# PatientBedAdapter.net
KiCad netlist of a schematic drawn in EAGLE
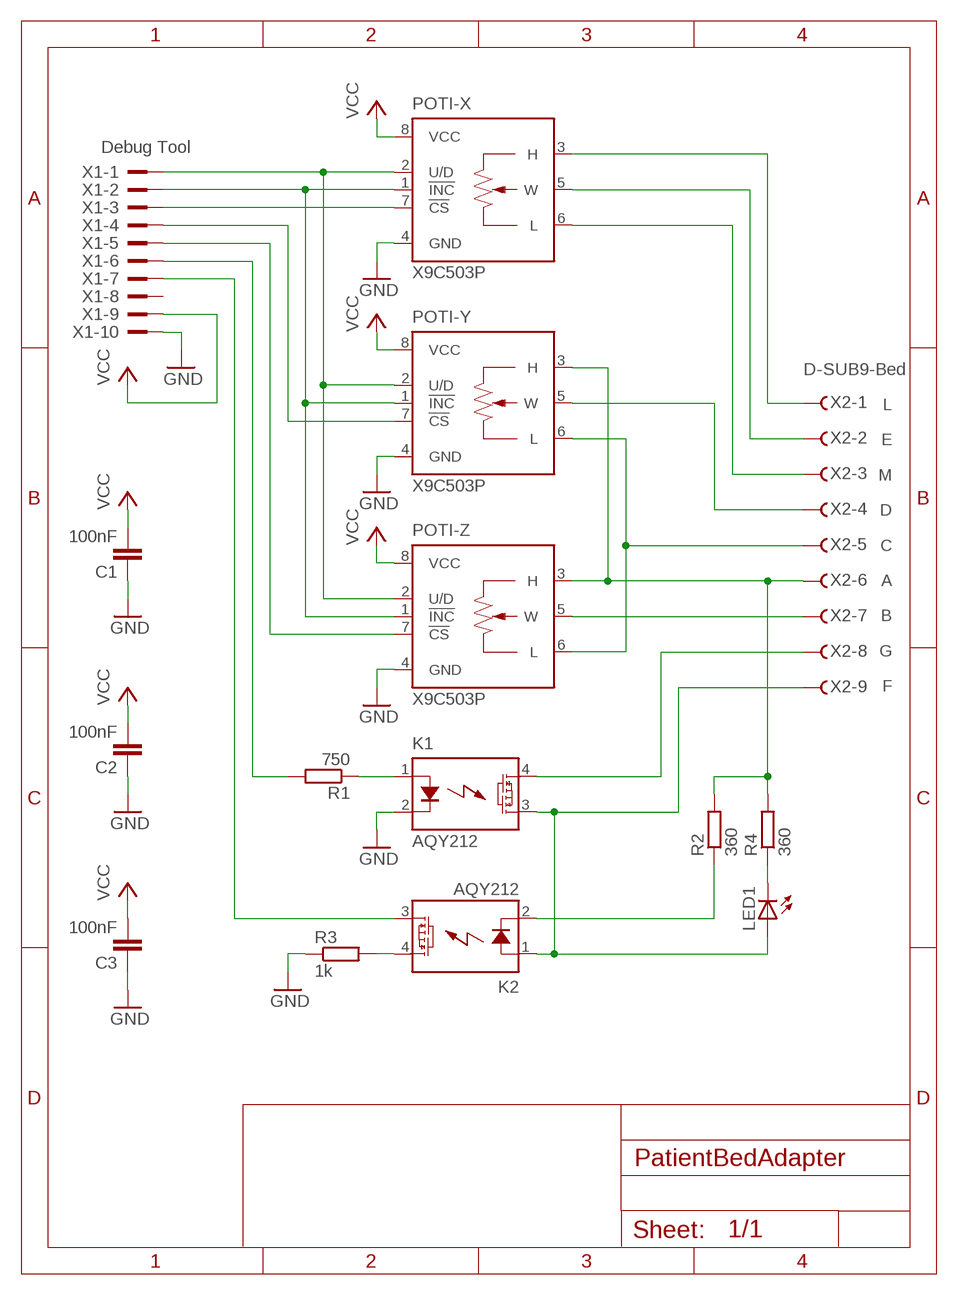
[diagram p0: schematic, sheet 1]

(export (version "E")
  (design (tool "Eeschema 10.0.6"))
  (components
    (comp (ref "C1")
      (value "100nF")
      (footprint "eagle-import:C050-024X044")
      (libsource (lib "eagle-import") (part "C-EU050-024X044"))
    )
    (comp (ref "C2")
      (value "100nF")
      (footprint "eagle-import:C050-024X044")
      (libsource (lib "eagle-import") (part "C-EU050-024X044"))
    )
    (comp (ref "C3")
      (value "100nF")
      (footprint "eagle-import:C050-024X044")
      (libsource (lib "eagle-import") (part "C-EU050-024X044"))
    )
    (comp (ref "K1")
      (value "AQY212")
      (footprint "eagle-import:SOP04")
      (libsource (lib "eagle-import") (part "AQYSOP21"))
    )
    (comp (ref "K2")
      (value "AQY212")
      (footprint "eagle-import:SOP04")
      (libsource (lib "eagle-import") (part "AQYSOP21"))
    )
    (comp (ref "LED1")
      (value "LED3MM")
      (footprint "eagle-import:LED3MM")
      (libsource (lib "eagle-import") (part "LED3MM"))
    )
    (comp (ref "POTI-X")
      (value "X9C503P")
      (footprint "eagle-import:DIL08")
      (fields (field (name "MF") "INTERSIL") (field (name "MPN") "X9C102P"))
      (libsource (lib "eagle-import") (part "X9C102P"))
    )
    (comp (ref "POTI-Y")
      (value "X9C503P")
      (footprint "eagle-import:DIL08")
      (fields (field (name "MF") "INTERSIL") (field (name "MPN") "X9C102P"))
      (libsource (lib "eagle-import") (part "X9C102P"))
    )
    (comp (ref "POTI-Z")
      (value "X9C503P")
      (footprint "eagle-import:DIL08")
      (fields (field (name "MF") "INTERSIL") (field (name "MPN") "X9C102P"))
      (libsource (lib "eagle-import") (part "X9C102P"))
    )
    (comp (ref "R1")
      (value "750")
      (footprint "eagle-import:R1206")
      (libsource (lib "eagle-import") (part "R-EU_R1206"))
    )
    (comp (ref "R2")
      (value "360")
      (footprint "eagle-import:R1206")
      (libsource (lib "eagle-import") (part "R-EU_R1206"))
    )
    (comp (ref "R3")
      (value "1k")
      (footprint "eagle-import:R1206")
      (libsource (lib "eagle-import") (part "R-EU_R1206"))
    )
    (comp (ref "R4")
      (value "360")
      (footprint "eagle-import:R1206")
      (libsource (lib "eagle-import") (part "R-EU_R1206"))
    )
    (comp (ref "X1")
      (value "Debug Tool")
      (footprint "eagle-import:PAK100_2500-10")
      (fields (field (name "MF") "3M") (field (name "MPN") "2510-6002UB"))
      (libsource (lib "eagle-import") (part "2510-"))
    )
    (comp (ref "X2")
      (value "D-SUB9-Bed")
      (footprint "eagle-import:H5M09RA")
      (libsource (lib "eagle-import") (part "D-SUB9-H5M09RA"))
    )
  )
  (nets
    (net (code "1") (name "GND") (class "Default")
      (node (ref "C1") (pin "1") (pinfunction "1_1") (pintype "passive"))
      (node (ref "C2") (pin "1") (pinfunction "1_1") (pintype "passive"))
      (node (ref "C3") (pin "1") (pinfunction "1_1") (pintype "passive"))
      (node (ref "K1") (pin "2") (pinfunction "K_2") (pintype "passive"))
      (node (ref "POTI-X") (pin "4") (pinfunction "GND_4") (pintype "power_in"))
      (node (ref "POTI-Y") (pin "4") (pinfunction "GND_4") (pintype "power_in"))
      (node (ref "POTI-Z") (pin "4") (pinfunction "GND_4") (pintype "power_in"))
      (node (ref "R3") (pin "1") (pinfunction "1_1") (pintype "passive"))
      (node (ref "X1") (pin "10") (pinfunction "KL_10") (pintype "passive"))
    )
    (net (code "2") (name "Net-(K1-A)") (class "Default")
      (node (ref "K1") (pin "1") (pinfunction "A_1") (pintype "passive"))
      (node (ref "R1") (pin "1") (pinfunction "1_1") (pintype "passive"))
    )
    (net (code "3") (name "Net-(K1-DS1)") (class "Default")
      (node (ref "K1") (pin "4") (pinfunction "DS1_4") (pintype "passive"))
      (node (ref "X2") (pin "8") (pinfunction "F_8") (pintype "passive"))
    )
    (net (code "4") (name "Net-(K1-DS2)") (class "Default")
      (node (ref "K1") (pin "3") (pinfunction "DS2_3") (pintype "passive"))
      (node (ref "K2") (pin "1") (pinfunction "A_1") (pintype "passive"))
      (node (ref "LED1") (pin "A") (pinfunction "A_A") (pintype "passive"))
      (node (ref "X2") (pin "9") (pinfunction "F_9") (pintype "passive"))
    )
    (net (code "5") (name "Net-(K2-DS1)") (class "Default")
      (node (ref "K2") (pin "4") (pinfunction "DS1_4") (pintype "passive"))
      (node (ref "R3") (pin "2") (pinfunction "2_2") (pintype "passive"))
    )
    (net (code "6") (name "Net-(K2-DS2)") (class "Default")
      (node (ref "K2") (pin "3") (pinfunction "DS2_3") (pintype "passive"))
      (node (ref "X1") (pin "7") (pinfunction "KL_7") (pintype "passive"))
    )
    (net (code "7") (name "Net-(K2-K)") (class "Default")
      (node (ref "K2") (pin "2") (pinfunction "K_2") (pintype "passive"))
      (node (ref "R2") (pin "1") (pinfunction "1_1") (pintype "passive"))
    )
    (net (code "8") (name "Net-(LED1-C)") (class "Default")
      (node (ref "LED1") (pin "K") (pinfunction "C_K") (pintype "passive"))
      (node (ref "R4") (pin "1") (pinfunction "1_1") (pintype "passive"))
    )
    (net (code "9") (name "Net-(POTI-X-H)") (class "Default")
      (node (ref "POTI-X") (pin "3") (pinfunction "H_3") (pintype "passive"))
      (node (ref "X2") (pin "1") (pinfunction "F_1") (pintype "passive"))
    )
    (net (code "10") (name "Net-(POTI-X-L)") (class "Default")
      (node (ref "POTI-X") (pin "6") (pinfunction "L_6") (pintype "passive"))
      (node (ref "X2") (pin "3") (pinfunction "F_3") (pintype "passive"))
    )
    (net (code "11") (name "Net-(POTI-X-U{slash}D)") (class "Default")
      (node (ref "POTI-X") (pin "2") (pinfunction "U/D_2") (pintype "input"))
      (node (ref "POTI-Y") (pin "2") (pinfunction "U/D_2") (pintype "input"))
      (node (ref "POTI-Z") (pin "2") (pinfunction "U/D_2") (pintype "input"))
      (node (ref "X1") (pin "1") (pinfunction "KL_1") (pintype "passive"))
    )
    (net (code "12") (name "Net-(POTI-X-W)") (class "Default")
      (node (ref "POTI-X") (pin "5") (pinfunction "W_5") (pintype "passive"))
      (node (ref "X2") (pin "2") (pinfunction "F_2") (pintype "passive"))
    )
    (net (code "13") (name "Net-(POTI-X-~{CS})") (class "Default")
      (node (ref "POTI-X") (pin "7") (pinfunction "~{CS}_7") (pintype "input"))
      (node (ref "X1") (pin "3") (pinfunction "KL_3") (pintype "passive"))
    )
    (net (code "14") (name "Net-(POTI-X-~{INC})") (class "Default")
      (node (ref "POTI-X") (pin "1") (pinfunction "~{INC}_1") (pintype "input"))
      (node (ref "POTI-Y") (pin "1") (pinfunction "~{INC}_1") (pintype "input"))
      (node (ref "POTI-Z") (pin "1") (pinfunction "~{INC}_1") (pintype "input"))
      (node (ref "X1") (pin "2") (pinfunction "KL_2") (pintype "passive"))
    )
    (net (code "15") (name "Net-(POTI-Y-H)") (class "Default")
      (node (ref "POTI-Y") (pin "3") (pinfunction "H_3") (pintype "passive"))
      (node (ref "POTI-Z") (pin "3") (pinfunction "H_3") (pintype "passive"))
      (node (ref "R2") (pin "2") (pinfunction "2_2") (pintype "passive"))
      (node (ref "R4") (pin "2") (pinfunction "2_2") (pintype "passive"))
      (node (ref "X2") (pin "6") (pinfunction "F_6") (pintype "passive"))
    )
    (net (code "16") (name "Net-(POTI-Y-L)") (class "Default")
      (node (ref "POTI-Y") (pin "6") (pinfunction "L_6") (pintype "passive"))
      (node (ref "POTI-Z") (pin "6") (pinfunction "L_6") (pintype "passive"))
      (node (ref "X2") (pin "5") (pinfunction "F_5") (pintype "passive"))
    )
    (net (code "17") (name "Net-(POTI-Y-W)") (class "Default")
      (node (ref "POTI-Y") (pin "5") (pinfunction "W_5") (pintype "passive"))
      (node (ref "X2") (pin "4") (pinfunction "F_4") (pintype "passive"))
    )
    (net (code "18") (name "Net-(POTI-Y-~{CS})") (class "Default")
      (node (ref "POTI-Y") (pin "7") (pinfunction "~{CS}_7") (pintype "input"))
      (node (ref "X1") (pin "4") (pinfunction "KL_4") (pintype "passive"))
    )
    (net (code "19") (name "Net-(POTI-Z-W)") (class "Default")
      (node (ref "POTI-Z") (pin "5") (pinfunction "W_5") (pintype "passive"))
      (node (ref "X2") (pin "7") (pinfunction "F_7") (pintype "passive"))
    )
    (net (code "20") (name "Net-(POTI-Z-~{CS})") (class "Default")
      (node (ref "POTI-Z") (pin "7") (pinfunction "~{CS}_7") (pintype "input"))
      (node (ref "X1") (pin "5") (pinfunction "KL_5") (pintype "passive"))
    )
    (net (code "21") (name "Net-(X1G-KL)") (class "Default")
      (node (ref "R1") (pin "2") (pinfunction "2_2") (pintype "passive"))
      (node (ref "X1") (pin "6") (pinfunction "KL_6") (pintype "passive"))
    )
    (net (code "22") (name "VCC") (class "Default")
      (node (ref "C1") (pin "2") (pinfunction "2_2") (pintype "passive"))
      (node (ref "C2") (pin "2") (pinfunction "2_2") (pintype "passive"))
      (node (ref "C3") (pin "2") (pinfunction "2_2") (pintype "passive"))
      (node (ref "POTI-X") (pin "8") (pinfunction "VCC_8") (pintype "power_in"))
      (node (ref "POTI-Y") (pin "8") (pinfunction "VCC_8") (pintype "power_in"))
      (node (ref "POTI-Z") (pin "8") (pinfunction "VCC_8") (pintype "power_in"))
      (node (ref "X1") (pin "9") (pinfunction "KL_9") (pintype "passive"))
    )
    (net (code "23") (name "unconnected-(X1I-KL-Pad8)") (class "Default")
      (node (ref "X1") (pin "8") (pinfunction "KL_8") (pintype "passive"))
    )
  )
)
